# powerSupply.net
KiCad netlist of a schematic drawn in Altium Designer
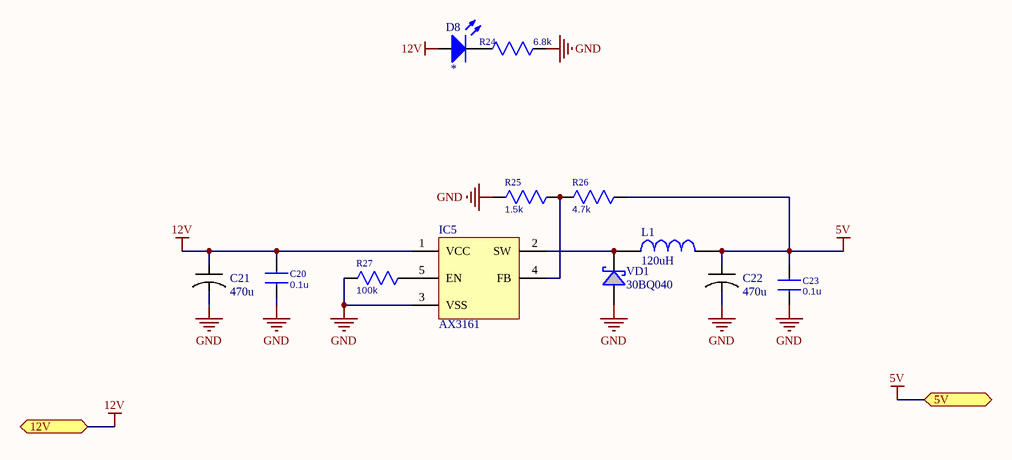
[diagram p0: powerSupply.SchDoc]

(export (version "E")
  (design (tool "Eeschema 10.0.6"))
  (components
    (comp (ref "C20")
      (value "0.1u")
      (footprint "C_0603")
      (description "Capacitor")
      (libsource (lib "AX_Altium_v2.3") (part "C0603"))
    )
    (comp (ref "C21")
      (value "470u")
      (footprint "ELV471M25RF")
      (description "Electrolit capasitor")
      (libsource (lib "SmartOutletIntegratedLibrary") (part "Electrolit"))
    )
    (comp (ref "C22")
      (value "470u")
      (footprint "ELV471M25RF")
      (description "Electrolit capasitor")
      (libsource (lib "SmartOutletIntegratedLibrary") (part "Electrolit"))
    )
    (comp (ref "C23")
      (value "0.1u")
      (footprint "C_0603")
      (description "Capacitor")
      (libsource (lib "AX_Altium_v2.3") (part "C0603"))
    )
    (comp (ref "D8")
      (value "*")
      (footprint "LED_5mm")
      (description "Typical INFRARED GaAs LED")
      (libsource (lib "AX_Altium_v2.3") (part "LED_5mm"))
    )
    (comp (ref "IC5")
      (value "AX3161")
      (footprint "TO263-5L")
      (description "52KHz, 2A PWM Buck DC/DC Converter")
      (libsource (lib "SmartOutletIntegratedLibrary") (part "AX3161"))
    )
    (comp (ref "L1")
      (value "120uH")
      (footprint "L-12.3x12.3")
      (description "Inductor")
      (libsource (lib "SmartOutletIntegratedLibrary") (part "L"))
    )
    (comp (ref "R24")
      (value "6.8k")
      (footprint "R_0603")
      (description "Resistor")
      (libsource (lib "AX_Altium_v2.3") (part "R0603"))
    )
    (comp (ref "R25")
      (value "1.5k")
      (footprint "R_0603")
      (description "Resistor")
      (libsource (lib "AX_Altium_v2.3") (part "R0603"))
    )
    (comp (ref "R26")
      (value "4.7k")
      (footprint "R_0603")
      (description "Resistor")
      (libsource (lib "AX_Altium_v2.3") (part "R0603"))
    )
    (comp (ref "R27")
      (value "100k")
      (footprint "R_0603")
      (description "Resistor")
      (libsource (lib "AX_Altium_v2.3") (part "R0603"))
    )
    (comp (ref "VD1")
      (value "30BQ040")
      (footprint "DO-214AB (SMC)")
      (description "High Performance Schottky Rectifier, 3.0 A")
      (libsource (lib "SmartOutletIntegratedLibrary") (part "30BQ040"))
    )
  )
  (nets
    (net (code "1") (name "5V") (class "Default")
      (node (ref "C22") (pin "1") (pinfunction "1_1") (pintype "passive"))
      (node (ref "C23") (pin "2") (pintype "passive"))
      (node (ref "L1") (pin "2") (pinfunction "2_2") (pintype "passive"))
      (node (ref "R26") (pin "1") (pintype "passive"))
    )
    (net (code "2") (name "12V") (class "Default")
      (node (ref "C20") (pin "2") (pintype "passive"))
      (node (ref "C21") (pin "1") (pinfunction "1_1") (pintype "passive"))
      (node (ref "D8") (pin "1") (pinfunction "A_1") (pintype "passive"))
      (node (ref "IC5") (pin "1") (pinfunction "VCC_1") (pintype "passive"))
    )
    (net (code "3") (name "GND") (class "Default")
      (node (ref "C20") (pin "1") (pintype "passive"))
      (node (ref "C21") (pin "2") (pinfunction "2_2") (pintype "passive"))
      (node (ref "C22") (pin "2") (pinfunction "2_2") (pintype "passive"))
      (node (ref "C23") (pin "1") (pintype "passive"))
      (node (ref "IC5") (pin "3") (pinfunction "VSS_3") (pintype "passive"))
      (node (ref "R24") (pin "2") (pintype "passive"))
      (node (ref "R25") (pin "2") (pintype "passive"))
      (node (ref "R27") (pin "2") (pintype "passive"))
      (node (ref "VD1") (pin "A") (pinfunction "A_A") (pintype "passive"))
    )
    (net (code "4") (name "Net-(D8-K)") (class "Default")
      (node (ref "D8") (pin "2") (pinfunction "K_2") (pintype "passive"))
      (node (ref "R24") (pin "1") (pintype "passive"))
    )
    (net (code "5") (name "Net-(IC5-EN)") (class "Default")
      (node (ref "IC5") (pin "5") (pinfunction "EN_5") (pintype "passive"))
      (node (ref "R27") (pin "1") (pintype "passive"))
    )
    (net (code "6") (name "Net-(IC5-FB)") (class "Default")
      (node (ref "IC5") (pin "4") (pinfunction "FB_4") (pintype "passive"))
      (node (ref "R25") (pin "1") (pintype "passive"))
      (node (ref "R26") (pin "2") (pintype "passive"))
    )
    (net (code "7") (name "Net-(IC5-SW)") (class "Default")
      (node (ref "IC5") (pin "2") (pinfunction "SW_2") (pintype "passive"))
      (node (ref "L1") (pin "1") (pinfunction "1_1") (pintype "passive"))
      (node (ref "VD1") (pin "C") (pinfunction "C_C") (pintype "passive"))
    )
  )
)
